# 2_Non_Volatile_Memories.net
KiCad netlist of a schematic drawn in Altium Designer
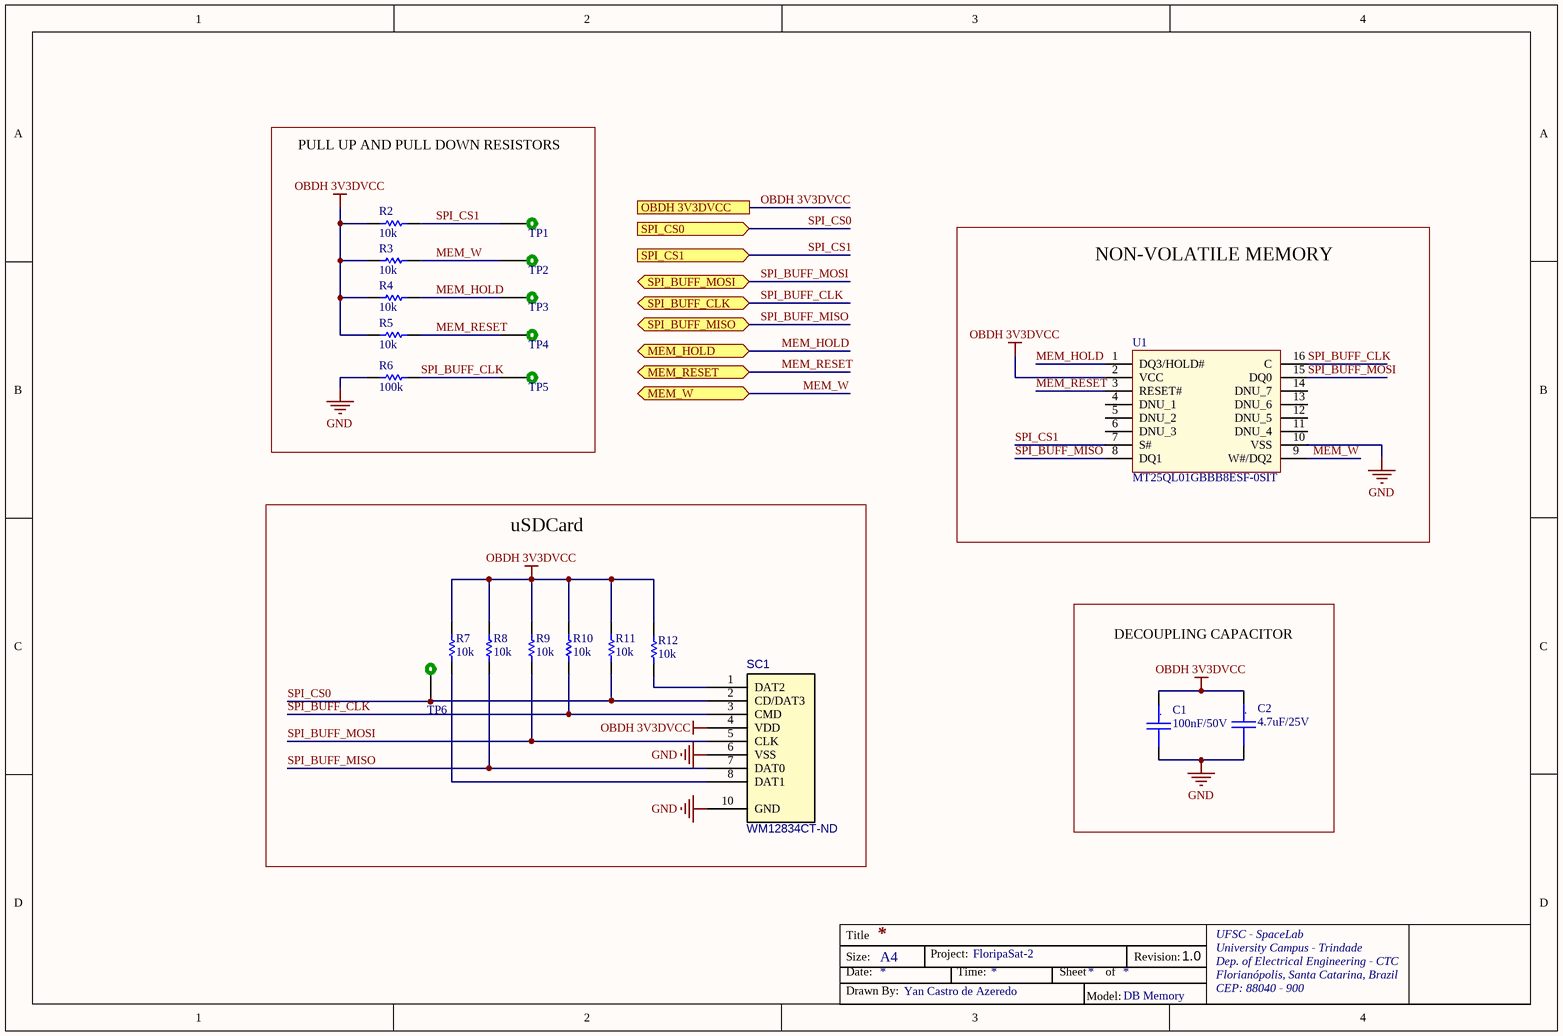
[diagram p0: 2_Non_Volatile_Memories.SchDoc]

(export (version "E")
  (design (tool "Eeschema 10.0.6"))
  (components
    (comp (ref "C1")
      (value "100nF/50V")
      (footprint "C0603_MD")
      (description "CAP CER 100nF 50V 0603 10%")
      (fields (field (name "PARTNUMBER") "C0603C104K5RAC3121"))
      (libsource (lib "Memory_Expansion_Daughter_Board_SchLib") (part "Cap_Cer_X7R_100nF_50V_0603"))
    )
    (comp (ref "C2")
      (value "4.7uF/25V")
      (footprint "C0805_MD")
      (description "CAP CER 4.7UF 25V 10% X7R 0805")
      (fields (field (name "PARTNUMBER") "C0805C475K3RACAUTO"))
      (libsource (lib "Memory_Expansion_Daughter_Board_SchLib") (part "Cap_Cer_X7R_4.7uF_25V_0805"))
    )
    (comp (ref "R2")
      (value "10k")
      (footprint "0805")
      (description "RES 10K OHM 1/8W 1%  0805")
      (fields (field (name "PARTNUMBER") "CRCW080510K0FKEA"))
      (libsource (lib "Memory_Expansion_Daughter_Board_SchLib") (part "R10k_1%_1/8W_0805"))
    )
    (comp (ref "R3")
      (value "10k")
      (footprint "0805")
      (description "RES 10K OHM 1/8W 1%  0805")
      (fields (field (name "PARTNUMBER") "CRCW080510K0FKEA"))
      (libsource (lib "Memory_Expansion_Daughter_Board_SchLib") (part "R10k_1%_1/8W_0805"))
    )
    (comp (ref "R4")
      (value "10k")
      (footprint "0805")
      (description "RES 10K OHM 1/8W 1%  0805")
      (fields (field (name "PARTNUMBER") "CRCW080510K0FKEA"))
      (libsource (lib "Memory_Expansion_Daughter_Board_SchLib") (part "R10k_1%_1/8W_0805"))
    )
    (comp (ref "R5")
      (value "10k")
      (footprint "0805")
      (description "RES 10K OHM 1/8W 1%  0805")
      (fields (field (name "PARTNUMBER") "CRCW080510K0FKEA"))
      (libsource (lib "Memory_Expansion_Daughter_Board_SchLib") (part "R10k_1%_1/8W_0805"))
    )
    (comp (ref "R6")
      (value "100k")
      (footprint "0805")
      (description "RES 100K OHM 1/8W 1% 0805")
      (fields (field (name "PARTNUMBER") "AC0805FR-13100KL"))
      (libsource (lib "Memory_Expansion_Daughter_Board_SchLib") (part "R100k_1%_1/8W_0805"))
    )
    (comp (ref "R7")
      (value "10k")
      (footprint "0805")
      (description "RES 10K OHM 1/8W 1%  0805")
      (fields (field (name "PARTNUMBER") "CRCW080510K0FKEA"))
      (libsource (lib "Memory_Expansion_Daughter_Board_SchLib") (part "R10k_1%_1/8W_0805"))
    )
    (comp (ref "R8")
      (value "10k")
      (footprint "0805")
      (description "RES 10K OHM 1/8W 1%  0805")
      (fields (field (name "PARTNUMBER") "CRCW080510K0FKEA"))
      (libsource (lib "Memory_Expansion_Daughter_Board_SchLib") (part "R10k_1%_1/8W_0805"))
    )
    (comp (ref "R9")
      (value "10k")
      (footprint "0805")
      (description "RES 10K OHM 1/8W 1%  0805")
      (fields (field (name "PARTNUMBER") "CRCW080510K0FKEA"))
      (libsource (lib "Memory_Expansion_Daughter_Board_SchLib") (part "R10k_1%_1/8W_0805"))
    )
    (comp (ref "R10")
      (value "10k")
      (footprint "0805")
      (description "RES 10K OHM 1/8W 1%  0805")
      (fields (field (name "PARTNUMBER") "CRCW080510K0FKEA"))
      (libsource (lib "Memory_Expansion_Daughter_Board_SchLib") (part "R10k_1%_1/8W_0805"))
    )
    (comp (ref "R11")
      (value "10k")
      (footprint "0805")
      (description "RES 10K OHM 1/8W 1%  0805")
      (fields (field (name "PARTNUMBER") "CRCW080510K0FKEA"))
      (libsource (lib "Memory_Expansion_Daughter_Board_SchLib") (part "R10k_1%_1/8W_0805"))
    )
    (comp (ref "R12")
      (value "10k")
      (footprint "0805")
      (description "RES 10K OHM 1/8W 1%  0805")
      (fields (field (name "PARTNUMBER") "CRCW080510K0FKEA"))
      (libsource (lib "Memory_Expansion_Daughter_Board_SchLib") (part "R10k_1%_1/8W_0805"))
    )
    (comp (ref "SC1")
      (value "WM12834CT-ND")
      (footprint "uSD_Card")
      (description "MicroSD CARD Connector")
      (libsource (lib "FloripaSatSchlib") (part "MicroSD_Card_Connector"))
    )
    (comp (ref "TP1")
      (value "TEST_POINT_2")
      (footprint "TEST_POINT_2")
      (description "Test point")
      (libsource (lib "Memory_Expansion_Daughter_Board_SchLib") (part "TEST_POINT_2"))
    )
    (comp (ref "TP2")
      (value "TEST_POINT_2")
      (footprint "TEST_POINT_2")
      (description "Test point")
      (libsource (lib "Memory_Expansion_Daughter_Board_SchLib") (part "TEST_POINT_2"))
    )
    (comp (ref "TP3")
      (value "TEST_POINT_2")
      (footprint "TEST_POINT_2")
      (description "Test point")
      (libsource (lib "Memory_Expansion_Daughter_Board_SchLib") (part "TEST_POINT_2"))
    )
    (comp (ref "TP4")
      (value "TEST_POINT_2")
      (footprint "TEST_POINT_2")
      (description "Test point")
      (libsource (lib "Memory_Expansion_Daughter_Board_SchLib") (part "TEST_POINT_2"))
    )
    (comp (ref "TP5")
      (value "TEST_POINT_2")
      (footprint "TEST_POINT_2")
      (description "Test point")
      (libsource (lib "Memory_Expansion_Daughter_Board_SchLib") (part "TEST_POINT_2"))
    )
    (comp (ref "TP6")
      (value "TEST_POINT_2")
      (footprint "TEST_POINT_2")
      (description "Test point")
      (libsource (lib "Memory_Expansion_Daughter_Board_SchLib") (part "TEST_POINT_2"))
    )
    (comp (ref "U1")
      (value "MT25QL01GBBB8ESF-0SIT")
      (footprint "SOIC127P1032X265-16N")
      (description "IC FLASH 1GBIT 108MHZ 16SOIC")
      (fields (field (name "MOUSER PART NUMBER") "340-278808-TRAY"))
      (libsource (lib "OBDH_Eng_Model_2_ALT") (part "MT25QL01GBBB8ESF-0SIT"))
    )
  )
  (nets
    (net (code "1") (name "/MEM_HOLD") (class "Default")
      (node (ref "R4") (pin "1") (pinfunction "1_1") (pintype "passive"))
      (node (ref "TP3") (pin "1") (pinfunction "1_1") (pintype "passive"))
      (node (ref "U1") (pin "1") (pinfunction "DQ3/HOLD#_1") (pintype "passive"))
    )
    (net (code "2") (name "/MEM_RESET") (class "Default")
      (node (ref "R5") (pin "1") (pinfunction "1_1") (pintype "passive"))
      (node (ref "TP4") (pin "1") (pinfunction "1_1") (pintype "passive"))
      (node (ref "U1") (pin "3") (pinfunction "RESET#_3") (pintype "passive"))
    )
    (net (code "3") (name "/MEM_W") (class "Default")
      (node (ref "R3") (pin "1") (pinfunction "1_1") (pintype "passive"))
      (node (ref "TP2") (pin "1") (pinfunction "1_1") (pintype "passive"))
      (node (ref "U1") (pin "9") (pinfunction "W#/DQ2_9") (pintype "passive"))
    )
    (net (code "4") (name "/SPI_BUFF_CLK") (class "Default")
      (node (ref "R10") (pin "1") (pinfunction "1_1") (pintype "passive"))
      (node (ref "R6") (pin "1") (pinfunction "1_1") (pintype "passive"))
      (node (ref "SC1") (pin "3") (pinfunction "CMD_3") (pintype "passive"))
      (node (ref "TP5") (pin "1") (pinfunction "1_1") (pintype "passive"))
      (node (ref "U1") (pin "16") (pinfunction "C_16") (pintype "passive"))
    )
    (net (code "5") (name "/SPI_BUFF_MISO") (class "Default")
      (node (ref "R8") (pin "1") (pinfunction "1_1") (pintype "passive"))
      (node (ref "SC1") (pin "7") (pinfunction "DAT0_7") (pintype "passive"))
      (node (ref "U1") (pin "8") (pinfunction "DQ1_8") (pintype "passive"))
    )
    (net (code "6") (name "/SPI_BUFF_MOSI") (class "Default")
      (node (ref "R9") (pin "1") (pinfunction "1_1") (pintype "passive"))
      (node (ref "SC1") (pin "5") (pinfunction "CLK_5") (pintype "passive"))
      (node (ref "U1") (pin "15") (pinfunction "DQ0_15") (pintype "passive"))
    )
    (net (code "7") (name "/SPI_CS0") (class "Default")
      (node (ref "R11") (pin "1") (pinfunction "1_1") (pintype "passive"))
      (node (ref "SC1") (pin "2") (pinfunction "CD/DAT3_2") (pintype "passive"))
      (node (ref "TP6") (pin "1") (pinfunction "1_1") (pintype "passive"))
    )
    (net (code "8") (name "/SPI_CS1") (class "Default")
      (node (ref "R2") (pin "1") (pinfunction "1_1") (pintype "passive"))
      (node (ref "TP1") (pin "1") (pinfunction "1_1") (pintype "passive"))
      (node (ref "U1") (pin "7") (pinfunction "S#_7") (pintype "passive"))
    )
    (net (code "9") (name "GND") (class "Default")
      (node (ref "C1") (pin "2") (pinfunction "2_2") (pintype "passive"))
      (node (ref "C2") (pin "2") (pinfunction "2_2") (pintype "passive"))
      (node (ref "R6") (pin "2") (pinfunction "2_2") (pintype "passive"))
      (node (ref "SC1") (pin "10") (pinfunction "GND_10") (pintype "passive"))
      (node (ref "SC1") (pin "6") (pinfunction "VSS_6") (pintype "passive"))
      (node (ref "U1") (pin "10") (pinfunction "VSS_10") (pintype "passive"))
    )
    (net (code "10") (name "Net-(SC1-DAT1)") (class "Default")
      (node (ref "R7") (pin "1") (pinfunction "1_1") (pintype "passive"))
      (node (ref "SC1") (pin "8") (pinfunction "DAT1_8") (pintype "passive"))
    )
    (net (code "11") (name "Net-(SC1-DAT2)") (class "Default")
      (node (ref "R12") (pin "1") (pinfunction "1_1") (pintype "passive"))
      (node (ref "SC1") (pin "1") (pinfunction "DAT2_1") (pintype "passive"))
    )
    (net (code "12") (name "OBDH 3V3DVCC") (class "Default")
      (node (ref "C1") (pin "1") (pinfunction "1_1") (pintype "passive"))
      (node (ref "C2") (pin "1") (pinfunction "1_1") (pintype "passive"))
      (node (ref "R10") (pin "2") (pinfunction "2_2") (pintype "passive"))
      (node (ref "R11") (pin "2") (pinfunction "2_2") (pintype "passive"))
      (node (ref "R12") (pin "2") (pinfunction "2_2") (pintype "passive"))
      (node (ref "R2") (pin "2") (pinfunction "2_2") (pintype "passive"))
      (node (ref "R3") (pin "2") (pinfunction "2_2") (pintype "passive"))
      (node (ref "R4") (pin "2") (pinfunction "2_2") (pintype "passive"))
      (node (ref "R5") (pin "2") (pinfunction "2_2") (pintype "passive"))
      (node (ref "R7") (pin "2") (pinfunction "2_2") (pintype "passive"))
      (node (ref "R8") (pin "2") (pinfunction "2_2") (pintype "passive"))
      (node (ref "R9") (pin "2") (pinfunction "2_2") (pintype "passive"))
      (node (ref "SC1") (pin "4") (pinfunction "VDD_4") (pintype "passive"))
      (node (ref "U1") (pin "2") (pinfunction "VCC_2") (pintype "passive"))
    )
    (net (code "13") (name "unconnected-(U1-DNU_1-Pad4)") (class "Default")
      (node (ref "U1") (pin "4") (pinfunction "DNU_1_4") (pintype "passive"))
    )
    (net (code "14") (name "unconnected-(U1-DNU_2-Pad5)") (class "Default")
      (node (ref "U1") (pin "5") (pinfunction "DNU_2_5") (pintype "passive"))
    )
    (net (code "15") (name "unconnected-(U1-DNU_3-Pad6)") (class "Default")
      (node (ref "U1") (pin "6") (pinfunction "DNU_3_6") (pintype "passive"))
    )
    (net (code "16") (name "unconnected-(U1-DNU_4-Pad11)") (class "Default")
      (node (ref "U1") (pin "11") (pinfunction "DNU_4_11") (pintype "passive"))
    )
    (net (code "17") (name "unconnected-(U1-DNU_5-Pad12)") (class "Default")
      (node (ref "U1") (pin "12") (pinfunction "DNU_5_12") (pintype "passive"))
    )
    (net (code "18") (name "unconnected-(U1-DNU_6-Pad13)") (class "Default")
      (node (ref "U1") (pin "13") (pinfunction "DNU_6_13") (pintype "passive"))
    )
    (net (code "19") (name "unconnected-(U1-DNU_7-Pad14)") (class "Default")
      (node (ref "U1") (pin "14") (pinfunction "DNU_7_14") (pintype "passive"))
    )
  )
)
